# NEO7M_EVAL.net
KiCad netlist of a schematic drawn in Altium Designer
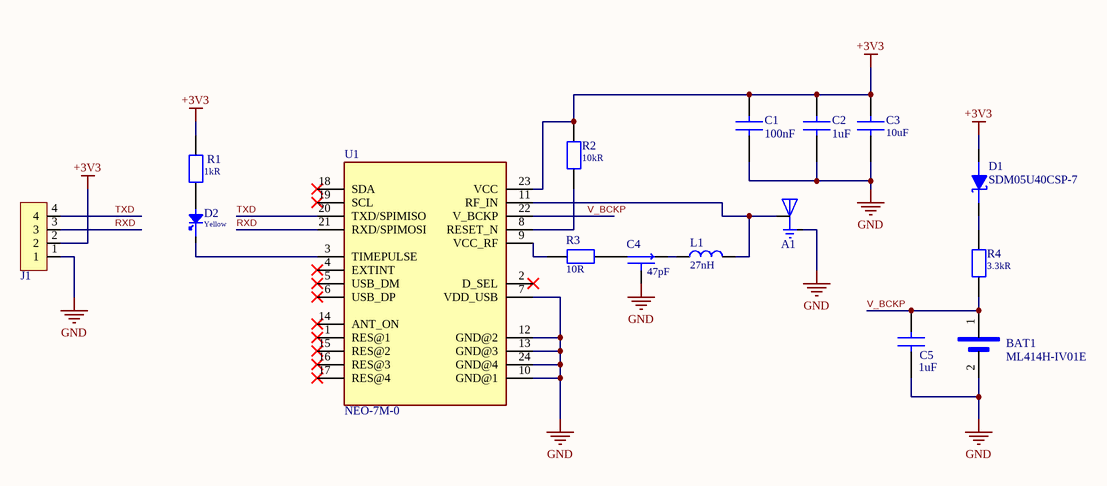
[diagram p0: NEO7M_EVAL.SchDoc]

(export (version "E")
  (design (tool "Eeschema 10.0.6"))
  (components
    (comp (ref "A1")
      (value "U.FL-R-SMT-1(10)")
      (footprint "HRS_U.FL-R-SMT-1(10)")
      (description "HIROSE(HRS) - U.FL-R-SMT-1(10) - RF COAXIAL, U.FL, STRAIGHT JACK, 50OHM")
      (fields (field (name "MANUFACTURER") "Hirose"))
      (libsource (lib "My_SCH_Lib") (part "U.FL-R-SMT-1(10)"))
    )
    (comp (ref "BAT1")
      (value "ML414H-IV01E")
      (footprint "ML414H-IV01E")
      (description "BATTERY LITHIUM 3V RECHARGE")
      (fields (field (name "MANUFACTURER") "Seiko"))
      (libsource (lib "Satellite_SchLib") (part "ML414H-IV01E"))
    )
    (comp (ref "C1")
      (value "C0603C104K5RAC7082")
      (footprint "CAP CER 0603")
      (description "Cap Cer 0.1uF 50V 0603 10%")
      (fields
        (field (name "MANUFACTURER") "KEMET")
        (field (name "TOLERANCE") "10%")
        (field (name "CAPACITANCE") "100nF")
        (field (name "DESIGNEDBY") "ENES MERCAN")
      )
      (libsource (lib "My_SCH_Lib") (part "CAP CER 0.1UF 50V 0603"))
    )
    (comp (ref "C2")
      (value "CL21B105KOFNFNE")
      (footprint "CAP CER 0805")
      (description "CAP CER 1UF 16V X7R 0805")
      (fields
        (field (name "MANUFACTURER") "Samsung")
        (field (name "TOLERANCE") "10%")
        (field (name "CAPACITANCE") "1uF")
      )
      (libsource (lib "My_SCH_Lib") (part "CAP CER 1UF 16V 0805"))
    )
    (comp (ref "C3")
      (value "GRM21BR61E106MA73L")
      (footprint "CAP CER 0805")
      (fields
        (field (name "MANUFACTURER") "Murata")
        (field (name "TOLERANCE") "20%")
        (field (name "CAPACITANCE") "10uF")
      )
      (libsource (lib "My_SCH_Lib") (part "CAP CER 10UF 25V 0805"))
    )
    (comp (ref "C4")
      (value "W2F11A4708AT1A")
      (footprint "CAP FEEDTRU 0805")
      (description "CAP FEEDTHRU 47PF 100V 0805")
      (fields
        (field (name "MANUFACTURER") "Kyocera AVX")
        (field (name "CAPACITANCE") "47pF")
        (field (name "TOLERANCE") "50%")
      )
      (libsource (lib "My_SCH_Lib") (part "CAP FT 47PF 100V 0805"))
    )
    (comp (ref "C5")
      (value "CL21B105KOFNFNE")
      (footprint "CAP CER 0805")
      (description "CAP CER 1UF 16V X7R 0805")
      (fields
        (field (name "MANUFACTURER") "Samsung")
        (field (name "TOLERANCE") "10%")
        (field (name "CAPACITANCE") "1uF")
      )
      (libsource (lib "Satellite_SchLib") (part "CAP CER 1UF 16V 0805"))
    )
    (comp (ref "D1")
      (value "SDM05U40CSP-7")
      (footprint "SDM05U40CSP-7")
      (description "DIODE SCHTKY 40V 500MA X3WLB1006")
      (fields (field (name "MANUFACTURER") "Diodes"))
      (libsource (lib "Satellite_SchLib") (part "Schottky Diode GPS"))
    )
    (comp (ref "D2")
      (value "APTD1608LSYCK/J3-PF")
      (footprint "LED GR 0603")
      (description "LED YELLOW CLEAR 2SMD")
      (fields (field (name "MANUFACTURER") "Kingbright") (field (name "COLOR") "Yellow"))
      (libsource (lib "My_SCH_Lib") (part "LED YLW 0603"))
    )
    (comp (ref "J1")
      (value "M20-9730445")
      (footprint "HDR_ML_1X4")
      (description "Headers & Wire Housings 04 SIL VERTICAL PIN HEADER GOLD HT")
      (fields (field (name "MANUFACTURER") "Harwin"))
      (libsource (lib "My_SCH_Lib") (part "HDR_ML_1X4"))
    )
    (comp (ref "L1")
      (value "LQG15HS27NJ02D")
      (footprint "IND 0402")
      (description "Inductor RF Chip Multi-Layer 27nH 5% 100MHz 8Q-Factor Air 300mA 460mOhm DCR 0402 Paper T/R")
      (fields
        (field (name "MANUFACTURER") "Murata")
        (field (name "TOLERANCE") "5%")
        (field (name "INDUCTANCE") "27nH")
      )
      (libsource (lib "My_SCH_Lib") (part "IND 27nH 0402"))
    )
    (comp (ref "R1")
      (value "RC0603FR-071KL")
      (footprint "RES 0603")
      (description "RES SMD 1K OHM 1% 1/10W 0603")
      (fields
        (field (name "MANUFACTURER") "Yageo")
        (field (name "TOLERANCE") "1%")
        (field (name "RESISTANCE") "1kR")
      )
      (libsource (lib "My_SCH_Lib") (part "RES 1KR 0603"))
    )
    (comp (ref "R2")
      (value "RC0603FR-0710KL")
      (footprint "RES 0603")
      (description "Res General Purpose Thick Film 0603 10K Ohm 1% 1/10W ±100ppm/°C Molded SMD Paper T/R")
      (fields
        (field (name "MANUFACTURER") "Yageo")
        (field (name "TOLERANCE") "1%")
        (field (name "RESISTANCE") "10kR")
      )
      (libsource (lib "My_SCH_Lib") (part "RES 10K 0603"))
    )
    (comp (ref "R3")
      (value "RK73H1ERTTP10R0F")
      (footprint "Res 0402")
      (description "Thick Film Resistors - SMD Anti Sulfur 0.5 Tol. 0402 -55oC to 155oC")
      (fields
        (field (name "MANUFACTURER") "KOA Speer")
        (field (name "TOLERANCE") "1%")
        (field (name "RESISTANCE") "10R")
      )
      (libsource (lib "Schlib1") (part "RES 10R 0402"))
    )
    (comp (ref "R4")
      (value "RC0603FR-073K3L")
      (footprint "RES 0603")
      (fields
        (field (name "MANUFACTURER") "Yageo")
        (field (name "TOLERANCE") "1%")
        (field (name "RESISTANCE") "3.3kR")
      )
      (libsource (lib "Satellite_SchLib") (part "RES 3K3R 0603"))
    )
    (comp (ref "U1")
      (value "NEO-7M-0")
      (footprint "NEO-7M-0")
      (description "series RF Receiver GLONASS, GNSS, GPS 1.575GHz -161dBm - - -")
      (fields (field (name "MANUFACTURER") "u-blox"))
      (libsource (lib "My_SCH_Lib") (part "NEO-7M-0"))
    )
  )
  (nets
    (net (code "1") (name "+3V3") (class "Default")
      (node (ref "C1") (pin "2") (pinfunction "2_2") (pintype "passive"))
      (node (ref "C2") (pin "2") (pinfunction "2_2") (pintype "passive"))
      (node (ref "C3") (pin "2") (pinfunction "2_2") (pintype "passive"))
      (node (ref "D1") (pin "A") (pinfunction "A_A") (pintype "passive"))
      (node (ref "J1") (pin "2") (pinfunction "2_2") (pintype "passive"))
      (node (ref "R1") (pin "2") (pinfunction "2_2") (pintype "passive"))
      (node (ref "R2") (pin "2") (pinfunction "2_2") (pintype "passive"))
      (node (ref "U1") (pin "23") (pinfunction "VCC_23") (pintype "power_in"))
    )
    (net (code "2") (name "/RXD") (class "Default")
      (node (ref "J1") (pin "3") (pinfunction "3_3") (pintype "passive"))
      (node (ref "U1") (pin "21") (pinfunction "RXD/SPIMOSI_21") (pintype "power_in"))
    )
    (net (code "3") (name "/TXD") (class "Default")
      (node (ref "J1") (pin "4") (pinfunction "4_4") (pintype "passive"))
      (node (ref "U1") (pin "20") (pinfunction "TXD/SPIMISO_20") (pintype "power_in"))
    )
    (net (code "4") (name "/V_BCKP") (class "Default")
      (node (ref "BAT1") (pin "1") (pinfunction "POS_1") (pintype "passive"))
      (node (ref "C5") (pin "2") (pinfunction "2_2") (pintype "passive"))
      (node (ref "R4") (pin "1") (pinfunction "1_1") (pintype "passive"))
      (node (ref "U1") (pin "22") (pinfunction "V_BCKP_22") (pintype "power_in"))
    )
    (net (code "5") (name "GND") (class "Default")
      (node (ref "A1") (pin "GND") (pinfunction "GND_GND") (pintype "passive"))
      (node (ref "BAT1") (pin "2") (pinfunction "NEG_2") (pintype "passive"))
      (node (ref "C1") (pin "1") (pinfunction "1_1") (pintype "passive"))
      (node (ref "C2") (pin "1") (pinfunction "1_1") (pintype "passive"))
      (node (ref "C3") (pin "1") (pinfunction "1_1") (pintype "passive"))
      (node (ref "C4") (pin "3") (pinfunction "3_3") (pintype "passive"))
      (node (ref "C5") (pin "1") (pinfunction "1_1") (pintype "passive"))
      (node (ref "J1") (pin "1") (pinfunction "1_1") (pintype "passive"))
      (node (ref "U1") (pin "10") (pinfunction "GND@1_10") (pintype "power_in"))
      (node (ref "U1") (pin "12") (pinfunction "GND@2_12") (pintype "power_in"))
      (node (ref "U1") (pin "13") (pinfunction "GND@3_13") (pintype "power_in"))
      (node (ref "U1") (pin "24") (pinfunction "GND@4_24") (pintype "power_in"))
      (node (ref "U1") (pin "7") (pinfunction "VDD_USB_7") (pintype "power_in"))
    )
    (net (code "6") (name "Net-(C4-Pad1)") (class "Default")
      (node (ref "C4") (pin "1") (pinfunction "1_1") (pintype "passive"))
      (node (ref "R3") (pin "2") (pinfunction "2_2") (pintype "passive"))
    )
    (net (code "7") (name "Net-(C4-Pad2)") (class "Default")
      (node (ref "C4") (pin "2") (pinfunction "2_2") (pintype "passive"))
      (node (ref "L1") (pin "1") (pinfunction "1_1") (pintype "passive"))
    )
    (net (code "8") (name "Net-(D1-PadC)") (class "Default")
      (node (ref "D1") (pin "C") (pinfunction "C_C") (pintype "passive"))
      (node (ref "R4") (pin "2") (pinfunction "2_2") (pintype "passive"))
    )
    (net (code "9") (name "Net-(D2-Pad2)") (class "Default")
      (node (ref "D2") (pin "2") (pinfunction "2_2") (pintype "passive"))
      (node (ref "R1") (pin "1") (pinfunction "1_1") (pintype "passive"))
    )
    (net (code "10") (name "Net-(U1-RESET_N)") (class "Default")
      (node (ref "R2") (pin "1") (pinfunction "1_1") (pintype "passive"))
      (node (ref "U1") (pin "8") (pinfunction "RESET_N_8") (pintype "power_in"))
    )
    (net (code "11") (name "Net-(U1-RF_IN)") (class "Default")
      (node (ref "A1") (pin "SIG") (pinfunction "SIG_SIG") (pintype "passive"))
      (node (ref "L1") (pin "2") (pinfunction "2_2") (pintype "passive"))
      (node (ref "U1") (pin "11") (pinfunction "RF_IN_11") (pintype "power_in"))
    )
    (net (code "12") (name "Net-(U1-TIMEPULSE)") (class "Default")
      (node (ref "D2") (pin "1") (pinfunction "1_1") (pintype "passive"))
      (node (ref "U1") (pin "3") (pinfunction "TIMEPULSE_3") (pintype "power_in"))
    )
    (net (code "13") (name "Net-(U1-VCC_RF)") (class "Default")
      (node (ref "R3") (pin "1") (pinfunction "1_1") (pintype "passive"))
      (node (ref "U1") (pin "9") (pinfunction "VCC_RF_9") (pintype "power_in"))
    )
    (net (code "14") (name "unconnected-(U1-ANT_ON-Pad14)") (class "Default")
      (node (ref "U1") (pin "14") (pinfunction "ANT_ON_14") (pintype "power_in+no_connect"))
    )
    (net (code "15") (name "unconnected-(U1-D_SEL-Pad2)") (class "Default")
      (node (ref "U1") (pin "2") (pinfunction "D_SEL_2") (pintype "power_in+no_connect"))
    )
    (net (code "16") (name "unconnected-(U1-EXTINT-Pad4)") (class "Default")
      (node (ref "U1") (pin "4") (pinfunction "EXTINT_4") (pintype "power_in+no_connect"))
    )
    (net (code "17") (name "unconnected-(U1-RES@1-Pad1)") (class "Default")
      (node (ref "U1") (pin "1") (pinfunction "RES@1_1") (pintype "power_in+no_connect"))
    )
    (net (code "18") (name "unconnected-(U1-RES@2-Pad15)") (class "Default")
      (node (ref "U1") (pin "15") (pinfunction "RES@2_15") (pintype "power_in+no_connect"))
    )
    (net (code "19") (name "unconnected-(U1-RES@3-Pad16)") (class "Default")
      (node (ref "U1") (pin "16") (pinfunction "RES@3_16") (pintype "power_in+no_connect"))
    )
    (net (code "20") (name "unconnected-(U1-RES@4-Pad17)") (class "Default")
      (node (ref "U1") (pin "17") (pinfunction "RES@4_17") (pintype "power_in+no_connect"))
    )
    (net (code "21") (name "unconnected-(U1-SCL-Pad19)") (class "Default")
      (node (ref "U1") (pin "19") (pinfunction "SCL_19") (pintype "power_in+no_connect"))
    )
    (net (code "22") (name "unconnected-(U1-SDA-Pad18)") (class "Default")
      (node (ref "U1") (pin "18") (pinfunction "SDA_18") (pintype "power_in+no_connect"))
    )
    (net (code "23") (name "unconnected-(U1-USB_DM-Pad5)") (class "Default")
      (node (ref "U1") (pin "5") (pinfunction "USB_DM_5") (pintype "power_in+no_connect"))
    )
    (net (code "24") (name "unconnected-(U1-USB_DP-Pad6)") (class "Default")
      (node (ref "U1") (pin "6") (pinfunction "USB_DP_6") (pintype "power_in+no_connect"))
    )
  )
)
